# pcmtest_withboard.net
KiCad netlist of a schematic drawn in EAGLE
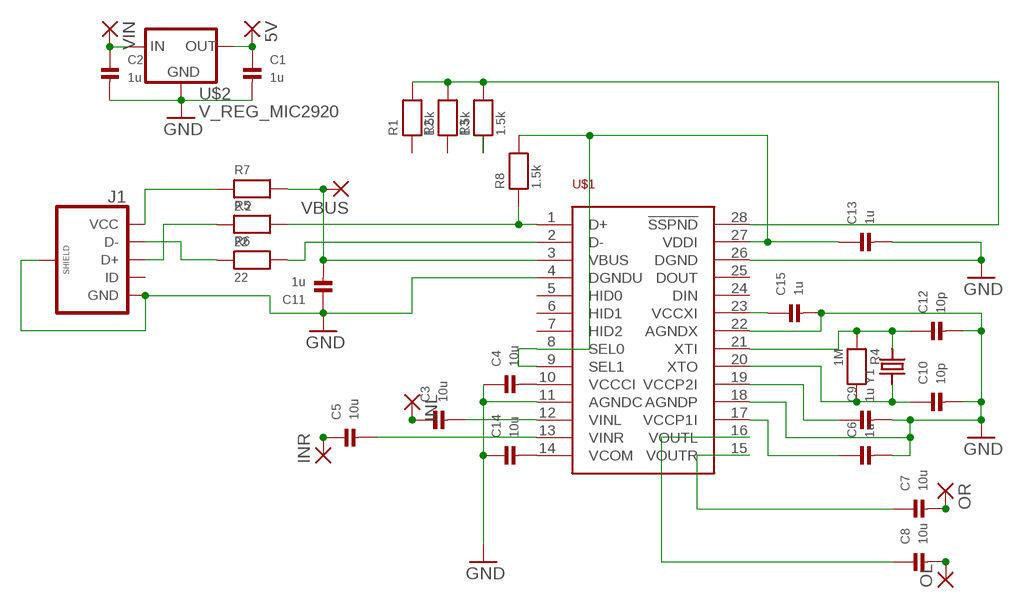
[diagram p0: schematic, sheet 1]

(export (version "E")
  (design (tool "Eeschema 10.0.6"))
  (components
    (comp (ref "5V")
      (value "SMD2")
      (footprint "eagle-import:SMD1,27-2,54")
      (libsource (lib "eagle-import") (part "SMD2"))
    )
    (comp (ref "C1")
      (value "1u")
      (footprint "eagle-import:_0603")
      (libsource (lib "eagle-import") (part "CAP_CERAMIC_0603"))
    )
    (comp (ref "C2")
      (value "1u")
      (footprint "eagle-import:_0603")
      (libsource (lib "eagle-import") (part "CAP_CERAMIC_0603"))
    )
    (comp (ref "C3")
      (value "10u")
      (footprint "eagle-import:_0603")
      (libsource (lib "eagle-import") (part "CAP_CERAMIC_0603"))
    )
    (comp (ref "C4")
      (value "10u")
      (footprint "eagle-import:_0603")
      (libsource (lib "eagle-import") (part "CAP_CERAMIC_0603"))
    )
    (comp (ref "C5")
      (value "10u")
      (footprint "eagle-import:_0603")
      (libsource (lib "eagle-import") (part "CAP_CERAMIC_0603"))
    )
    (comp (ref "C6")
      (value "1u")
      (footprint "eagle-import:_0603")
      (libsource (lib "eagle-import") (part "CAP_CERAMIC_0603"))
    )
    (comp (ref "C7")
      (value "10u")
      (footprint "eagle-import:_0603")
      (libsource (lib "eagle-import") (part "CAP_CERAMIC_0603"))
    )
    (comp (ref "C8")
      (value "10u")
      (footprint "eagle-import:_0603")
      (libsource (lib "eagle-import") (part "CAP_CERAMIC_0603"))
    )
    (comp (ref "C9")
      (value "1u")
      (footprint "eagle-import:_0603")
      (libsource (lib "eagle-import") (part "CAP_CERAMIC_0603"))
    )
    (comp (ref "C10")
      (value "10p")
      (footprint "eagle-import:_0603")
      (libsource (lib "eagle-import") (part "CAP_CERAMIC_0603"))
    )
    (comp (ref "C11")
      (value "1u")
      (footprint "eagle-import:_0603")
      (libsource (lib "eagle-import") (part "CAP_CERAMIC_0603"))
    )
    (comp (ref "C12")
      (value "10p")
      (footprint "eagle-import:_0603")
      (libsource (lib "eagle-import") (part "CAP_CERAMIC_0603"))
    )
    (comp (ref "C13")
      (value "1u")
      (footprint "eagle-import:_0603")
      (libsource (lib "eagle-import") (part "CAP_CERAMIC_0603"))
    )
    (comp (ref "C14")
      (value "10u")
      (footprint "eagle-import:_0603")
      (libsource (lib "eagle-import") (part "CAP_CERAMIC_0603"))
    )
    (comp (ref "C15")
      (value "1u")
      (footprint "eagle-import:_0603")
      (libsource (lib "eagle-import") (part "CAP_CERAMIC_0603"))
    )
    (comp (ref "INL")
      (value "SMD2")
      (footprint "eagle-import:SMD1,27-2,54")
      (libsource (lib "eagle-import") (part "SMD2"))
    )
    (comp (ref "INR")
      (value "SMD2")
      (footprint "eagle-import:SMD1,27-2,54")
      (libsource (lib "eagle-import") (part "SMD2"))
    )
    (comp (ref "J1")
      (value "USB_MICROB_PLUGCONN-11752")
      (footprint "eagle-import:USB-B-MICRO-SMD_V03")
      (libsource (lib "eagle-import") (part "USB_MICROB_PLUGCONN-11752"))
    )
    (comp (ref "OL")
      (value "SMD2")
      (footprint "eagle-import:SMD1,27-2,54")
      (libsource (lib "eagle-import") (part "SMD2"))
    )
    (comp (ref "OR")
      (value "SMD2")
      (footprint "eagle-import:SMD1,27-2,54")
      (libsource (lib "eagle-import") (part "SMD2"))
    )
    (comp (ref "R1")
      (value "1.5k")
      (footprint "eagle-import:_0603")
      (libsource (lib "eagle-import") (part "RESISTOR_0603"))
    )
    (comp (ref "R2")
      (value "1.5k")
      (footprint "eagle-import:_0603")
      (libsource (lib "eagle-import") (part "RESISTOR_0603"))
    )
    (comp (ref "R3")
      (value "1.5k")
      (footprint "eagle-import:_0603")
      (libsource (lib "eagle-import") (part "RESISTOR_0603"))
    )
    (comp (ref "R4")
      (value "1M")
      (footprint "eagle-import:_0603")
      (libsource (lib "eagle-import") (part "RESISTOR_0603"))
    )
    (comp (ref "R5")
      (value "22")
      (footprint "eagle-import:_0603")
      (libsource (lib "eagle-import") (part "RESISTOR_0603"))
    )
    (comp (ref "R6")
      (value "22")
      (footprint "eagle-import:_0603")
      (libsource (lib "eagle-import") (part "RESISTOR_0603"))
    )
    (comp (ref "R7")
      (value "2.2")
      (footprint "eagle-import:_0603")
      (libsource (lib "eagle-import") (part "RESISTOR_0603"))
    )
    (comp (ref "R8")
      (value "1.5k")
      (footprint "eagle-import:_0603")
      (libsource (lib "eagle-import") (part "RESISTOR_0603"))
    )
    (comp (ref "U$1")
      (value "PCM2906")
      (footprint "eagle-import:SSOP28")
      (libsource (lib "eagle-import") (part "PCM2906"))
    )
    (comp (ref "U$2")
      (value "V_REG_MIC2920")
      (footprint "eagle-import:SOT223")
      (libsource (lib "eagle-import") (part "V_REG_MIC2920"))
    )
    (comp (ref "VBUS")
      (value "SMD2")
      (footprint "eagle-import:SMD1,27-2,54")
      (libsource (lib "eagle-import") (part "SMD2"))
    )
    (comp (ref "VIN")
      (value "SMD2")
      (footprint "eagle-import:SMD1,27-2,54")
      (libsource (lib "eagle-import") (part "SMD2"))
    )
    (comp (ref "Y1")
      (value "CRYSTAL2.5X2.0MM")
      (footprint "eagle-import:CRYSTAL_2.5X2")
      (libsource (lib "eagle-import") (part "CRYSTAL2.5X2.0MM"))
    )
  )
  (nets
    (net (code "1") (name "GND") (class "Default")
      (node (ref "C1") (pin "2") (pinfunction "P$2_2") (pintype "passive"))
      (node (ref "C10") (pin "2") (pinfunction "P$2_2") (pintype "passive"))
      (node (ref "C11") (pin "1") (pinfunction "P$1_1") (pintype "passive"))
      (node (ref "C12") (pin "2") (pinfunction "P$2_2") (pintype "passive"))
      (node (ref "C13") (pin "2") (pinfunction "P$2_2") (pintype "passive"))
      (node (ref "C14") (pin "1") (pinfunction "P$1_1") (pintype "passive"))
      (node (ref "C15") (pin "2") (pinfunction "P$2_2") (pintype "passive"))
      (node (ref "C2") (pin "2") (pinfunction "P$2_2") (pintype "passive"))
      (node (ref "C4") (pin "1") (pinfunction "P$1_1") (pintype "passive"))
      (node (ref "C6") (pin "2") (pinfunction "P$2_2") (pintype "passive"))
      (node (ref "C9") (pin "2") (pinfunction "P$2_2") (pintype "passive"))
      (node (ref "J1") (pin "GND") (pinfunction "GND_GND") (pintype "bidirectional"))
      (node (ref "J1") (pin "SHIELD1") (pinfunction "SHIELD_SHIELD1") (pintype "bidirectional"))
      (node (ref "J1") (pin "SHIELD2") (pinfunction "SHIELD_SHIELD2") (pintype "bidirectional"))
      (node (ref "J1") (pin "SHIELD3") (pinfunction "SHIELD_SHIELD3") (pintype "bidirectional"))
      (node (ref "U$1") (pin "11") (pinfunction "AGNDC_11") (pintype "bidirectional"))
      (node (ref "U$1") (pin "18") (pinfunction "AGNDP_18") (pintype "bidirectional"))
      (node (ref "U$1") (pin "22") (pinfunction "AGNDX_22") (pintype "bidirectional"))
      (node (ref "U$1") (pin "26") (pinfunction "DGND_26") (pintype "bidirectional"))
      (node (ref "U$1") (pin "4") (pinfunction "DGNDU_4") (pintype "bidirectional"))
      (node (ref "U$2") (pin "2") (pinfunction "GND_2") (pintype "input"))
    )
    (net (code "2") (name "Net-(5V-P)") (class "Default")
      (node (ref "5V") (pin "1") (pinfunction "P_1") (pintype "passive"))
      (node (ref "C1") (pin "1") (pinfunction "P$1_1") (pintype "passive"))
      (node (ref "U$2") (pin "3") (pinfunction "OUT_3") (pintype "passive"))
    )
    (net (code "3") (name "Net-(C2-P$1)") (class "Default")
      (node (ref "C2") (pin "1") (pinfunction "P$1_1") (pintype "passive"))
      (node (ref "U$2") (pin "1") (pinfunction "IN_1") (pintype "input"))
      (node (ref "VIN") (pin "1") (pinfunction "P_1") (pintype "passive"))
    )
    (net (code "4") (name "Net-(C3-P$1)") (class "Default")
      (node (ref "C3") (pin "1") (pinfunction "P$1_1") (pintype "passive"))
      (node (ref "INL") (pin "1") (pinfunction "P_1") (pintype "passive"))
    )
    (net (code "5") (name "Net-(C3-P$2)") (class "Default")
      (node (ref "C3") (pin "2") (pinfunction "P$2_2") (pintype "passive"))
      (node (ref "U$1") (pin "12") (pinfunction "VINL_12") (pintype "bidirectional"))
    )
    (net (code "6") (name "Net-(C4-P$2)") (class "Default")
      (node (ref "C4") (pin "2") (pinfunction "P$2_2") (pintype "passive"))
      (node (ref "U$1") (pin "10") (pinfunction "VCCCI_10") (pintype "bidirectional"))
    )
    (net (code "7") (name "Net-(C5-P$1)") (class "Default")
      (node (ref "C5") (pin "1") (pinfunction "P$1_1") (pintype "passive"))
      (node (ref "INR") (pin "1") (pinfunction "P_1") (pintype "passive"))
    )
    (net (code "8") (name "Net-(C5-P$2)") (class "Default")
      (node (ref "C5") (pin "2") (pinfunction "P$2_2") (pintype "passive"))
      (node (ref "U$1") (pin "13") (pinfunction "VINR_13") (pintype "bidirectional"))
    )
    (net (code "9") (name "Net-(C6-P$1)") (class "Default")
      (node (ref "C6") (pin "1") (pinfunction "P$1_1") (pintype "passive"))
      (node (ref "U$1") (pin "17") (pinfunction "VCCP1I_17") (pintype "bidirectional"))
    )
    (net (code "10") (name "Net-(C7-P$1)") (class "Default")
      (node (ref "C7") (pin "1") (pinfunction "P$1_1") (pintype "passive"))
      (node (ref "U$1") (pin "15") (pinfunction "VOUTR_15") (pintype "bidirectional"))
    )
    (net (code "11") (name "Net-(C7-P$2)") (class "Default")
      (node (ref "C7") (pin "2") (pinfunction "P$2_2") (pintype "passive"))
      (node (ref "OR") (pin "1") (pinfunction "P_1") (pintype "passive"))
    )
    (net (code "12") (name "Net-(C8-P$1)") (class "Default")
      (node (ref "C8") (pin "1") (pinfunction "P$1_1") (pintype "passive"))
      (node (ref "U$1") (pin "16") (pinfunction "VOUTL_16") (pintype "bidirectional"))
    )
    (net (code "13") (name "Net-(C8-P$2)") (class "Default")
      (node (ref "C8") (pin "2") (pinfunction "P$2_2") (pintype "passive"))
      (node (ref "OL") (pin "1") (pinfunction "P_1") (pintype "passive"))
    )
    (net (code "14") (name "Net-(C9-P$1)") (class "Default")
      (node (ref "C9") (pin "1") (pinfunction "P$1_1") (pintype "passive"))
      (node (ref "U$1") (pin "19") (pinfunction "VCCP2I_19") (pintype "bidirectional"))
    )
    (net (code "15") (name "Net-(C10-P$1)") (class "Default")
      (node (ref "C10") (pin "1") (pinfunction "P$1_1") (pintype "passive"))
      (node (ref "R4") (pin "2") (pinfunction "2_2") (pintype "passive"))
      (node (ref "U$1") (pin "20") (pinfunction "XTO_20") (pintype "bidirectional"))
      (node (ref "Y1") (pin "1") (pinfunction "1_1") (pintype "passive"))
    )
    (net (code "16") (name "Net-(C11-P$2)") (class "Default")
      (node (ref "C11") (pin "2") (pinfunction "P$2_2") (pintype "passive"))
      (node (ref "R7") (pin "2") (pinfunction "2_2") (pintype "passive"))
      (node (ref "U$1") (pin "3") (pinfunction "VBUS_3") (pintype "bidirectional"))
      (node (ref "VBUS") (pin "1") (pinfunction "P_1") (pintype "passive"))
    )
    (net (code "17") (name "Net-(C12-P$1)") (class "Default")
      (node (ref "C12") (pin "1") (pinfunction "P$1_1") (pintype "passive"))
      (node (ref "R4") (pin "1") (pinfunction "1_1") (pintype "passive"))
      (node (ref "U$1") (pin "21") (pinfunction "XTI_21") (pintype "bidirectional"))
      (node (ref "Y1") (pin "3") (pinfunction "2_3") (pintype "passive"))
    )
    (net (code "18") (name "Net-(C13-P$1)") (class "Default")
      (node (ref "C13") (pin "1") (pinfunction "P$1_1") (pintype "passive"))
      (node (ref "R8") (pin "2") (pinfunction "2_2") (pintype "passive"))
      (node (ref "U$1") (pin "27") (pinfunction "VDDI_27") (pintype "bidirectional"))
      (node (ref "U$1") (pin "8") (pinfunction "SEL0_8") (pintype "bidirectional"))
      (node (ref "U$1") (pin "9") (pinfunction "SEL1_9") (pintype "bidirectional"))
    )
    (net (code "19") (name "Net-(C14-P$2)") (class "Default")
      (node (ref "C14") (pin "2") (pinfunction "P$2_2") (pintype "passive"))
      (node (ref "U$1") (pin "14") (pinfunction "VCOM_14") (pintype "bidirectional"))
    )
    (net (code "20") (name "Net-(C15-P$1)") (class "Default")
      (node (ref "C15") (pin "1") (pinfunction "P$1_1") (pintype "passive"))
      (node (ref "U$1") (pin "23") (pinfunction "VCCXI_23") (pintype "bidirectional"))
    )
    (net (code "21") (name "Net-(J1-PadD+)") (class "Default")
      (node (ref "J1") (pin "D+") (pinfunction "D+_D+") (pintype "bidirectional"))
      (node (ref "R5") (pin "1") (pinfunction "1_1") (pintype "passive"))
    )
    (net (code "22") (name "Net-(J1-PadD-)") (class "Default")
      (node (ref "J1") (pin "D-") (pinfunction "D-_D-") (pintype "bidirectional"))
      (node (ref "R6") (pin "1") (pinfunction "1_1") (pintype "passive"))
    )
    (net (code "23") (name "Net-(J1-VCC)") (class "Default")
      (node (ref "J1") (pin "VBUS") (pinfunction "VCC_VBUS") (pintype "bidirectional"))
      (node (ref "R7") (pin "1") (pinfunction "1_1") (pintype "passive"))
    )
    (net (code "24") (name "Net-(U$1-D+)") (class "Default")
      (node (ref "R5") (pin "2") (pinfunction "2_2") (pintype "passive"))
      (node (ref "R8") (pin "1") (pinfunction "1_1") (pintype "passive"))
      (node (ref "U$1") (pin "1") (pinfunction "D+_1") (pintype "bidirectional"))
    )
    (net (code "25") (name "Net-(U$1-D-)") (class "Default")
      (node (ref "R6") (pin "2") (pinfunction "2_2") (pintype "passive"))
      (node (ref "U$1") (pin "2") (pinfunction "D-_2") (pintype "bidirectional"))
    )
    (net (code "26") (name "Net-(U$1-~{SSPND})") (class "Default")
      (node (ref "R1") (pin "2") (pinfunction "2_2") (pintype "passive"))
      (node (ref "R2") (pin "2") (pinfunction "2_2") (pintype "passive"))
      (node (ref "R3") (pin "2") (pinfunction "2_2") (pintype "passive"))
      (node (ref "U$1") (pin "28") (pinfunction "~{SSPND}_28") (pintype "bidirectional"))
    )
    (net (code "27") (name "unconnected-(J1-PadID)") (class "Default")
      (node (ref "J1") (pin "ID") (pinfunction "ID_ID") (pintype "bidirectional"))
    )
    (net (code "28") (name "unconnected-(R1-Pad1)") (class "Default")
      (node (ref "R1") (pin "1") (pinfunction "1_1") (pintype "passive"))
    )
    (net (code "29") (name "unconnected-(R2-Pad1)") (class "Default")
      (node (ref "R2") (pin "1") (pinfunction "1_1") (pintype "passive"))
    )
    (net (code "30") (name "unconnected-(R3-Pad1)") (class "Default")
      (node (ref "R3") (pin "1") (pinfunction "1_1") (pintype "passive"))
    )
    (net (code "31") (name "unconnected-(U$1-DIN-Pad24)") (class "Default")
      (node (ref "U$1") (pin "24") (pinfunction "DIN_24") (pintype "bidirectional"))
    )
    (net (code "32") (name "unconnected-(U$1-DOUT-Pad25)") (class "Default")
      (node (ref "U$1") (pin "25") (pinfunction "DOUT_25") (pintype "bidirectional"))
    )
    (net (code "33") (name "unconnected-(U$1-HID0-Pad5)") (class "Default")
      (node (ref "U$1") (pin "5") (pinfunction "HID0_5") (pintype "bidirectional"))
    )
    (net (code "34") (name "unconnected-(U$1-HID1-Pad6)") (class "Default")
      (node (ref "U$1") (pin "6") (pinfunction "HID1_6") (pintype "bidirectional"))
    )
    (net (code "35") (name "unconnected-(U$1-HID2-Pad7)") (class "Default")
      (node (ref "U$1") (pin "7") (pinfunction "HID2_7") (pintype "bidirectional"))
    )
  )
)
